# CAN_System.net
KiCad netlist of a schematic drawn in Altium Designer
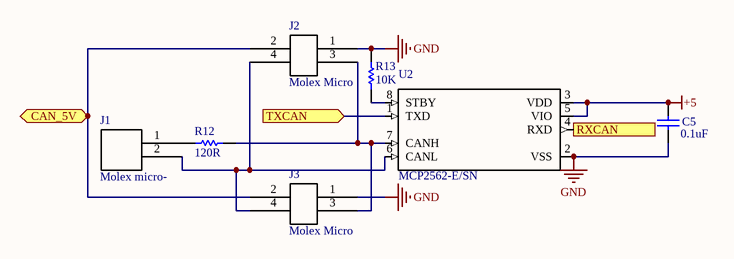
[diagram p0: CAN System.SchDoc]

(export (version "E")
  (design (tool "Eeschema 10.0.6"))
  (components
    (comp (ref "C5")
      (value "0.1uF")
      (footprint "CAPC2013X94X50LL20T25")
      (description "Chip Capacitor, 0.1 uF, +/- 5%, 50 V, -55 to 125 degC, 0805 (2012 Metric), RoHS, Tape and Reel")
      (fields (field (name "TOLERANCE") "5%") (field (name "MANUFACTURER") "AVX"))
      (libsource (lib "Altium Content Vault") (part "CAP-NP-2"))
    )
    (comp (ref "J1")
      (value "Molex micro-")
      (footprint "0430450227")
      (description "Molex micro-fit 3.0. Molex P/N 0430450227")
      (libsource (lib "Husky Robotics Standard Library 2019-2020") (part "Molex micro-fit 2-pin"))
    )
    (comp (ref "J2")
      (value "Molex Micro")
      (footprint "0430450427")
      (description "Molex micro-fit 3.0, P/N 0430450427")
      (libsource (lib "Husky Robotics Standard Library 2019-2020") (part "Molex micro-fit 4-pin (dual row schematic)"))
    )
    (comp (ref "J3")
      (value "Molex Micro")
      (footprint "0430450427")
      (description "Molex micro-fit 3.0, P/N 0430450427")
      (libsource (lib "Husky Robotics Standard Library 2019-2020") (part "Molex micro-fit 4-pin (dual row schematic)"))
    )
    (comp (ref "R12")
      (value "120R")
      (footprint "RESC0805(2012)_N")
      (description "120R 0.125W 5% 0805 (2012 Metric)  SMD")
      (fields (field (name "TOLERANCE") "5 %") (field (name "POWER") "0.125 W"))
      (libsource (lib "Husky Robotics Standard Library 2019-2020") (part "120R 5% 0805"))
    )
    (comp (ref "R13")
      (value "10K")
      (footprint "RESC0805(2012)_M")
      (description "1K 0.125W 1% 0805 (2012 Metric)  SMD")
      (fields (field (name "TOLERANCE") "1 %") (field (name "POWER") "0.125 W"))
      (libsource (lib "Altium Content Vault") (part "RES"))
    )
    (comp (ref "U2")
      (value "MCP2562-E/SN")
      (footprint "SOIC127P600X175-8N")
      (description "Microchip MCP2562-E/SN, CAN Transceiver 1MBps 1-channel IEC 61000-4-2, 8-Pin SOIC")
      (fields (field (name "MF") "Microchip"))
      (libsource (lib "Husky Robotics Standard Library 2019-2020") (part "MCP2562-E/SN"))
    )
  )
  (nets
    (net (code "1") (name "+5") (class "Default")
      (node (ref "C5") (pin "1") (pinfunction "1_1") (pintype "passive"))
      (node (ref "U2") (pin "3") (pinfunction "VDD_3") (pintype "power_in"))
      (node (ref "U2") (pin "5") (pinfunction "VIO_5") (pintype "power_in"))
    )
    (net (code "2") (name "/CAN_5V") (class "Default")
      (node (ref "J2") (pin "2") (pintype "passive"))
      (node (ref "J3") (pin "2") (pintype "passive"))
    )
    (net (code "3") (name "/RXCAN") (class "Default")
      (node (ref "U2") (pin "4") (pinfunction "RXD_4") (pintype "output"))
    )
    (net (code "4") (name "/TXCAN") (class "Default")
      (node (ref "U2") (pin "1") (pinfunction "TXD_1") (pintype "input"))
    )
    (net (code "5") (name "GND") (class "Default")
      (node (ref "C5") (pin "2") (pinfunction "2_2") (pintype "passive"))
      (node (ref "J2") (pin "1") (pintype "passive"))
      (node (ref "J3") (pin "1") (pintype "passive"))
      (node (ref "R13") (pin "2") (pinfunction "2_2") (pintype "passive"))
      (node (ref "U2") (pin "2") (pinfunction "VSS_2") (pintype "power_in"))
    )
    (net (code "6") (name "Net-(J1-Pad1)") (class "Default")
      (node (ref "J1") (pin "1") (pintype "passive"))
      (node (ref "R12") (pin "1") (pinfunction "1_1") (pintype "passive"))
    )
    (net (code "7") (name "Net-(U2-CANH)") (class "Default")
      (node (ref "J2") (pin "3") (pintype "passive"))
      (node (ref "J3") (pin "3") (pintype "passive"))
      (node (ref "R12") (pin "2") (pinfunction "2_2") (pintype "passive"))
      (node (ref "U2") (pin "7") (pinfunction "CANH_7") (pintype "input"))
    )
    (net (code "8") (name "Net-(U2-CANL)") (class "Default")
      (node (ref "J1") (pin "2") (pintype "passive"))
      (node (ref "J2") (pin "4") (pintype "passive"))
      (node (ref "J3") (pin "4") (pintype "passive"))
      (node (ref "U2") (pin "6") (pinfunction "CANL_6") (pintype "input"))
    )
    (net (code "9") (name "Net-(U2-STBY)") (class "Default")
      (node (ref "R13") (pin "1") (pinfunction "1_1") (pintype "passive"))
      (node (ref "U2") (pin "8") (pinfunction "STBY_8") (pintype "input"))
    )
  )
)
